# Flash.net
KiCad netlist of a schematic drawn in Altium Designer
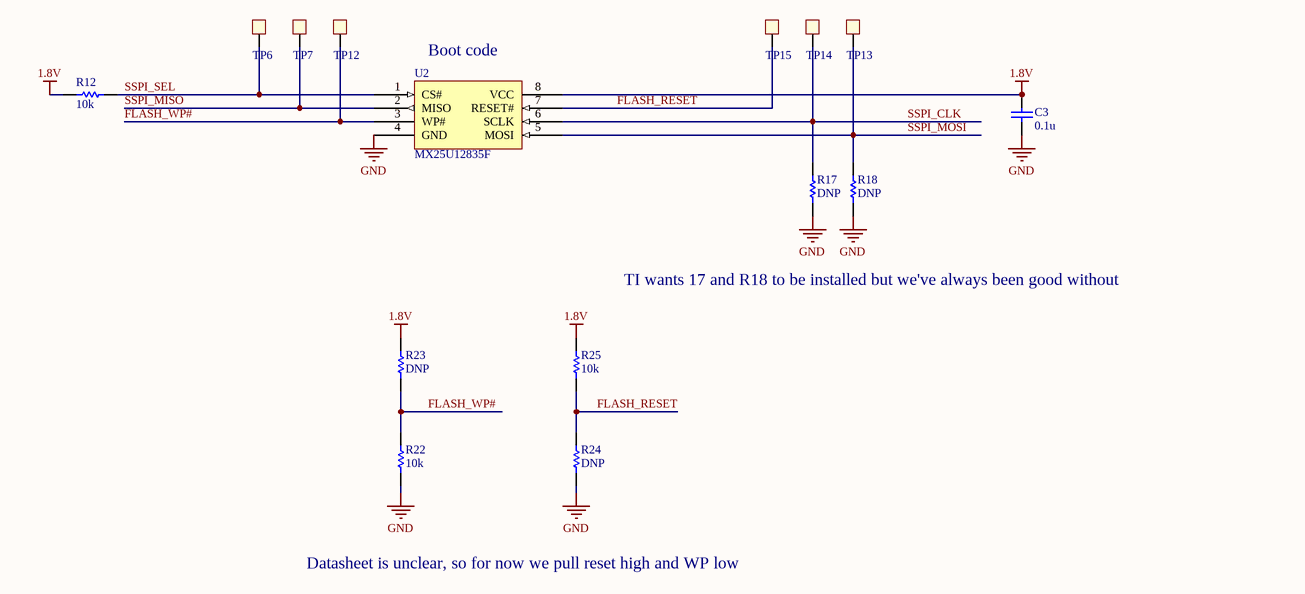
[diagram p0: Flash.SchDoc]

(export (version "E")
  (design (tool "Eeschema 10.0.6"))
  (components
    (comp (ref "C3")
      (value "0.1u")
      (footprint "CAP0402_SENSE_DVT")
      (description "Chip capacitor")
      (fields (field (name "TOLERANCE") "10%") (field (name "VOLTAGE") "50V"))
      (libsource (lib "Morpheus_pill") (part "C_0.1u_10_50_X7R_0402"))
    )
    (comp (ref "R12")
      (value "10k")
      (footprint "RES0402_SENSE_DVT")
      (description "Chip Resistor")
      (fields (field (name "TOLERANCE") "5 %") (field (name "POWER") "0.1 W"))
      (libsource (lib "Morpheus_pill") (part "R_10k_5_0.1_0402"))
    )
    (comp (ref "R17")
      (value "DNP")
      (footprint "RES0402_SENSE_DVT")
      (description "Chip Resistor")
      (fields (field (name "TOLERANCE") "1 %") (field (name "POWER") "0.1 W"))
      (libsource (lib "Morpheus_pill") (part "R_100k_1_0.1_0402"))
    )
    (comp (ref "R18")
      (value "DNP")
      (footprint "RES0402_SENSE_DVT")
      (description "Chip Resistor")
      (fields (field (name "TOLERANCE") "1 %") (field (name "POWER") "0.1 W"))
      (libsource (lib "Morpheus_pill") (part "R_100k_1_0.1_0402"))
    )
    (comp (ref "R22")
      (value "10k")
      (footprint "RES0402_SENSE_DVT")
      (description "Chip Resistor")
      (fields (field (name "TOLERANCE") "5 %") (field (name "POWER") "0.1 W"))
      (libsource (lib "Morpheus_pill") (part "R_10k_5_0.1_0402"))
    )
    (comp (ref "R23")
      (value "DNP")
      (footprint "RES0402_SENSE_DVT")
      (description "Chip Resistor")
      (fields (field (name "TOLERANCE") "5 %") (field (name "POWER") "0.1 W"))
      (libsource (lib "Morpheus_pill") (part "R_10k_5_0.1_0402"))
    )
    (comp (ref "R24")
      (value "DNP")
      (footprint "RES0402_SENSE_DVT")
      (description "Chip Resistor")
      (fields (field (name "TOLERANCE") "5 %") (field (name "POWER") "0.1 W"))
      (libsource (lib "Morpheus_pill") (part "R_10k_5_0.1_0402"))
    )
    (comp (ref "R25")
      (value "10k")
      (footprint "RES0402_SENSE_DVT")
      (description "Chip Resistor")
      (fields (field (name "TOLERANCE") "5 %") (field (name "POWER") "0.1 W"))
      (libsource (lib "Morpheus_pill") (part "R_10k_5_0.1_0402"))
    )
    (comp (ref "TP6")
      (value "TP")
      (footprint "TP-1.1")
      (description "testpoint")
      (libsource (lib "Morpheus_pill") (part "TP"))
    )
    (comp (ref "TP7")
      (value "TP")
      (footprint "TP-1.1")
      (description "testpoint")
      (libsource (lib "Morpheus_pill") (part "TP"))
    )
    (comp (ref "TP12")
      (value "TP")
      (footprint "TP-1.1")
      (description "testpoint")
      (libsource (lib "Morpheus_pill") (part "TP"))
    )
    (comp (ref "TP13")
      (value "TP")
      (footprint "TP-1.1")
      (description "testpoint")
      (libsource (lib "Morpheus_pill") (part "TP"))
    )
    (comp (ref "TP14")
      (value "TP")
      (footprint "TP-1.1")
      (description "testpoint")
      (libsource (lib "Morpheus_pill") (part "TP"))
    )
    (comp (ref "TP15")
      (value "TP")
      (footprint "TP-1.1")
      (description "testpoint")
      (libsource (lib "Morpheus_pill") (part "TP"))
    )
    (comp (ref "U2")
      (value "MX25U12835F")
      (footprint "WSON 8L")
      (description "Macronix MX25U12835F SPI NOR Flash")
      (libsource (lib "Morpheus_pill") (part "MX25U12835F"))
    )
  )
  (nets
    (net (code "1") (name "/FLASH_RESET") (class "Default")
      (node (ref "R24") (pin "2") (pinfunction "2_2") (pintype "passive"))
      (node (ref "R25") (pin "1") (pinfunction "1_1") (pintype "passive"))
      (node (ref "TP15") (pin "1") (pinfunction "1_1") (pintype "passive"))
      (node (ref "U2") (pin "7") (pinfunction "RESET#_7") (pintype "input"))
    )
    (net (code "2") (name "/FLASH_WP#") (class "Default")
      (node (ref "R22") (pin "2") (pinfunction "2_2") (pintype "passive"))
      (node (ref "R23") (pin "1") (pinfunction "1_1") (pintype "passive"))
      (node (ref "TP12") (pin "1") (pinfunction "1_1") (pintype "passive"))
      (node (ref "U2") (pin "3") (pinfunction "WP#_3") (pintype "passive"))
    )
    (net (code "3") (name "/SSPI_CLK") (class "Default")
      (node (ref "R17") (pin "2") (pinfunction "2_2") (pintype "passive"))
      (node (ref "TP14") (pin "1") (pinfunction "1_1") (pintype "passive"))
      (node (ref "U2") (pin "6") (pinfunction "SCLK_6") (pintype "input"))
    )
    (net (code "4") (name "/SSPI_MISO") (class "Default")
      (node (ref "TP7") (pin "1") (pinfunction "1_1") (pintype "passive"))
      (node (ref "U2") (pin "2") (pinfunction "MISO_2") (pintype "output"))
    )
    (net (code "5") (name "/SSPI_MOSI") (class "Default")
      (node (ref "R18") (pin "2") (pinfunction "2_2") (pintype "passive"))
      (node (ref "TP13") (pin "1") (pinfunction "1_1") (pintype "passive"))
      (node (ref "U2") (pin "5") (pinfunction "MOSI_5") (pintype "input"))
    )
    (net (code "6") (name "/SSPI_SEL") (class "Default")
      (node (ref "R12") (pin "2") (pinfunction "2_2") (pintype "passive"))
      (node (ref "TP6") (pin "1") (pinfunction "1_1") (pintype "passive"))
      (node (ref "U2") (pin "1") (pinfunction "CS#_1") (pintype "input"))
    )
    (net (code "7") (name "1.8V") (class "Default")
      (node (ref "C3") (pin "2") (pinfunction "2_2") (pintype "passive"))
      (node (ref "R12") (pin "1") (pinfunction "1_1") (pintype "passive"))
      (node (ref "R23") (pin "2") (pinfunction "2_2") (pintype "passive"))
      (node (ref "R25") (pin "2") (pinfunction "2_2") (pintype "passive"))
      (node (ref "U2") (pin "8") (pinfunction "VCC_8") (pintype "power_in"))
    )
    (net (code "8") (name "GND") (class "Default")
      (node (ref "C3") (pin "1") (pinfunction "1_1") (pintype "passive"))
      (node (ref "R17") (pin "1") (pinfunction "1_1") (pintype "passive"))
      (node (ref "R18") (pin "1") (pinfunction "1_1") (pintype "passive"))
      (node (ref "R22") (pin "1") (pinfunction "1_1") (pintype "passive"))
      (node (ref "R24") (pin "1") (pinfunction "1_1") (pintype "passive"))
      (node (ref "U2") (pin "4") (pinfunction "GND_4") (pintype "power_in"))
    )
  )
)
